# r3eflow-v1-outdated.net
KiCad netlist of a schematic drawn in EAGLE
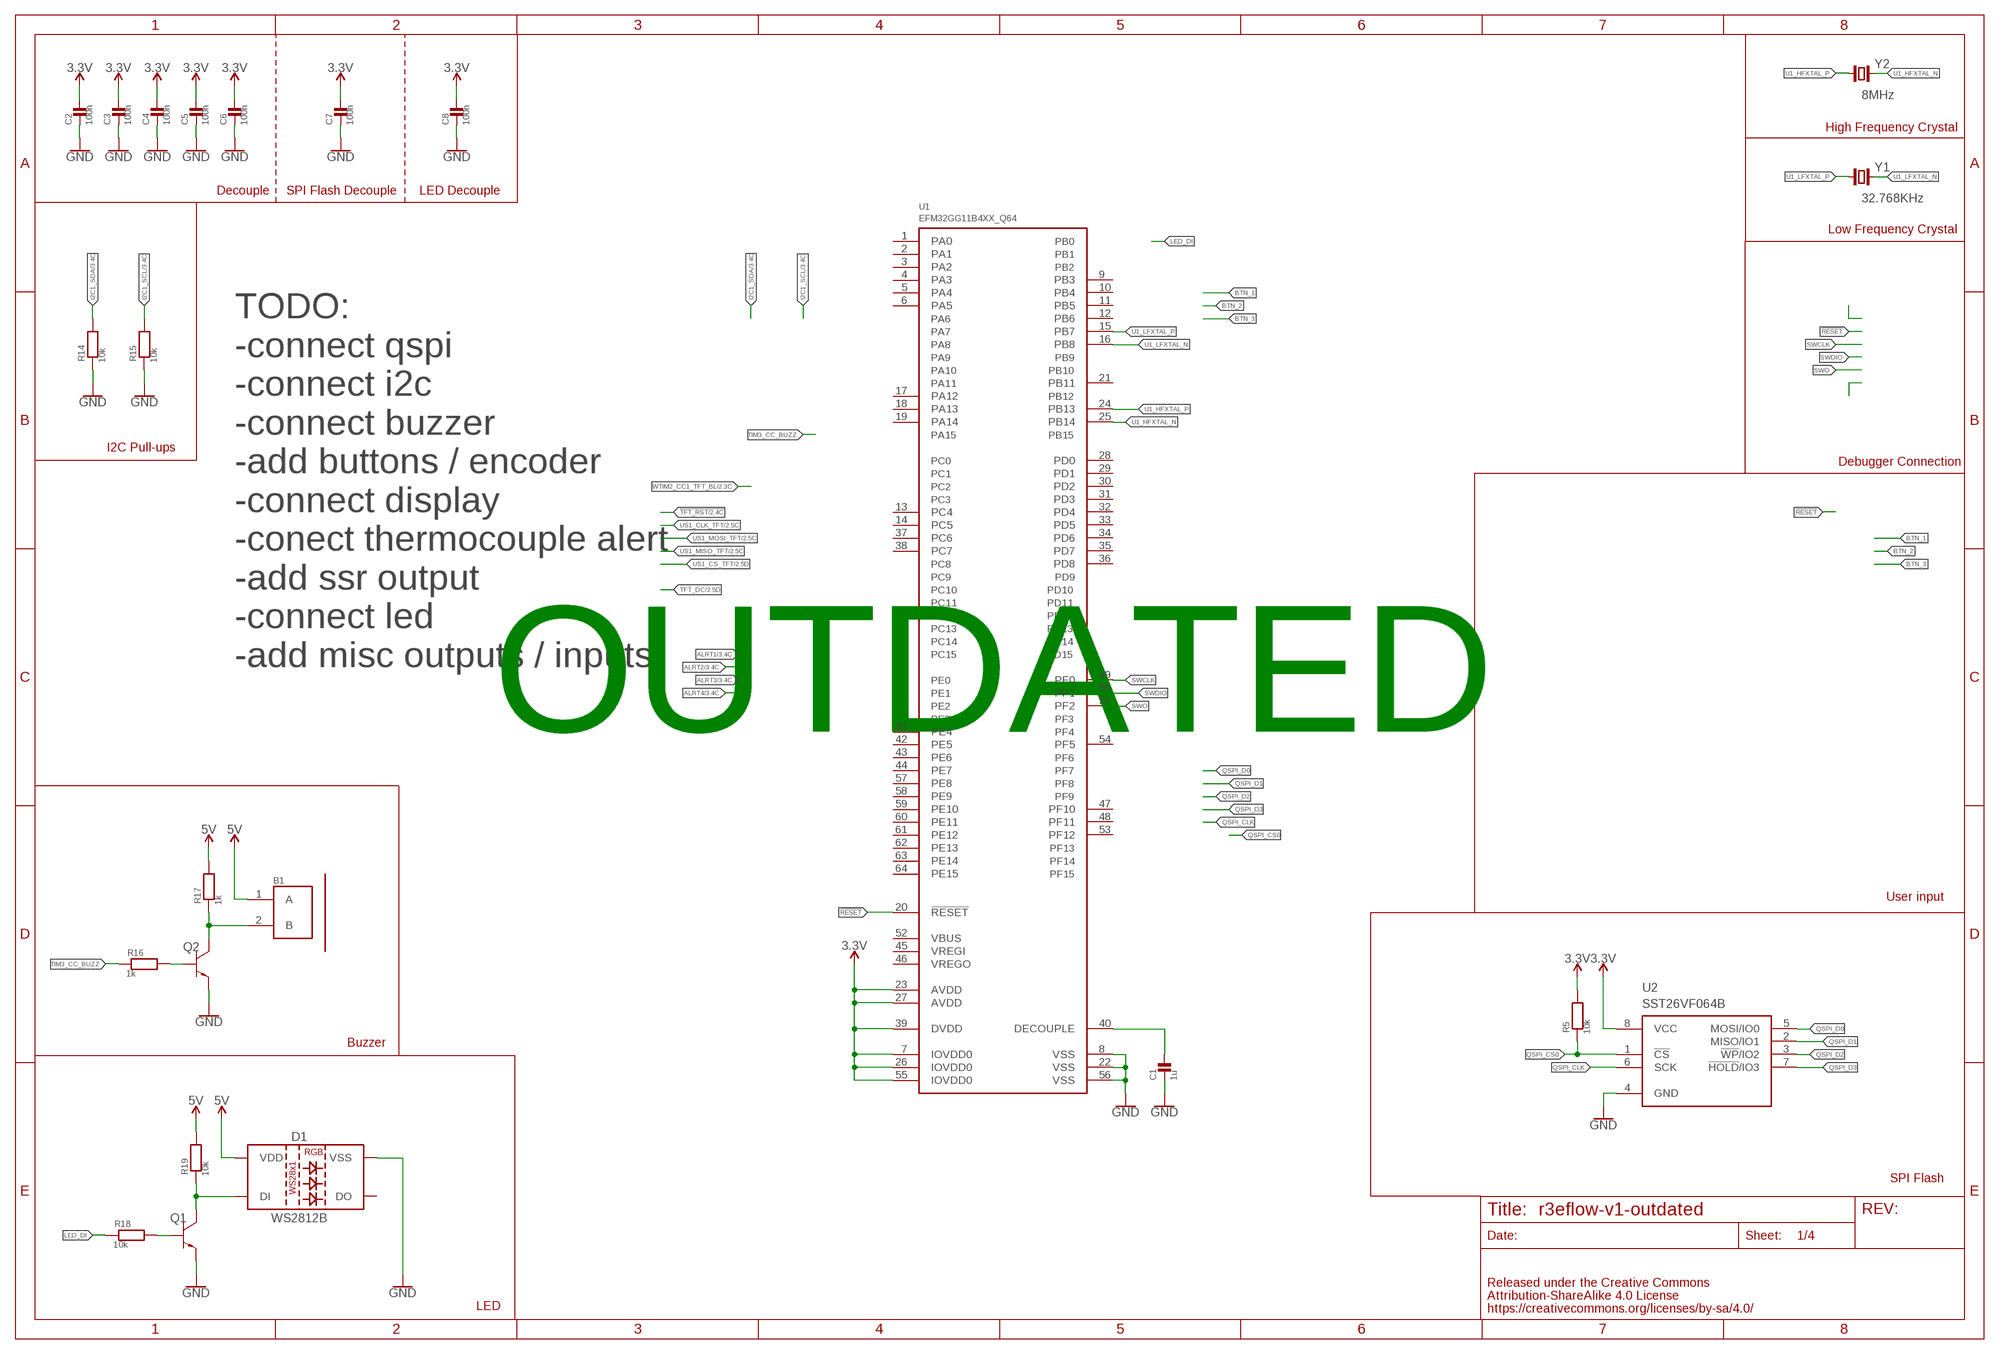
[diagram p0: schematic, sheet 1]
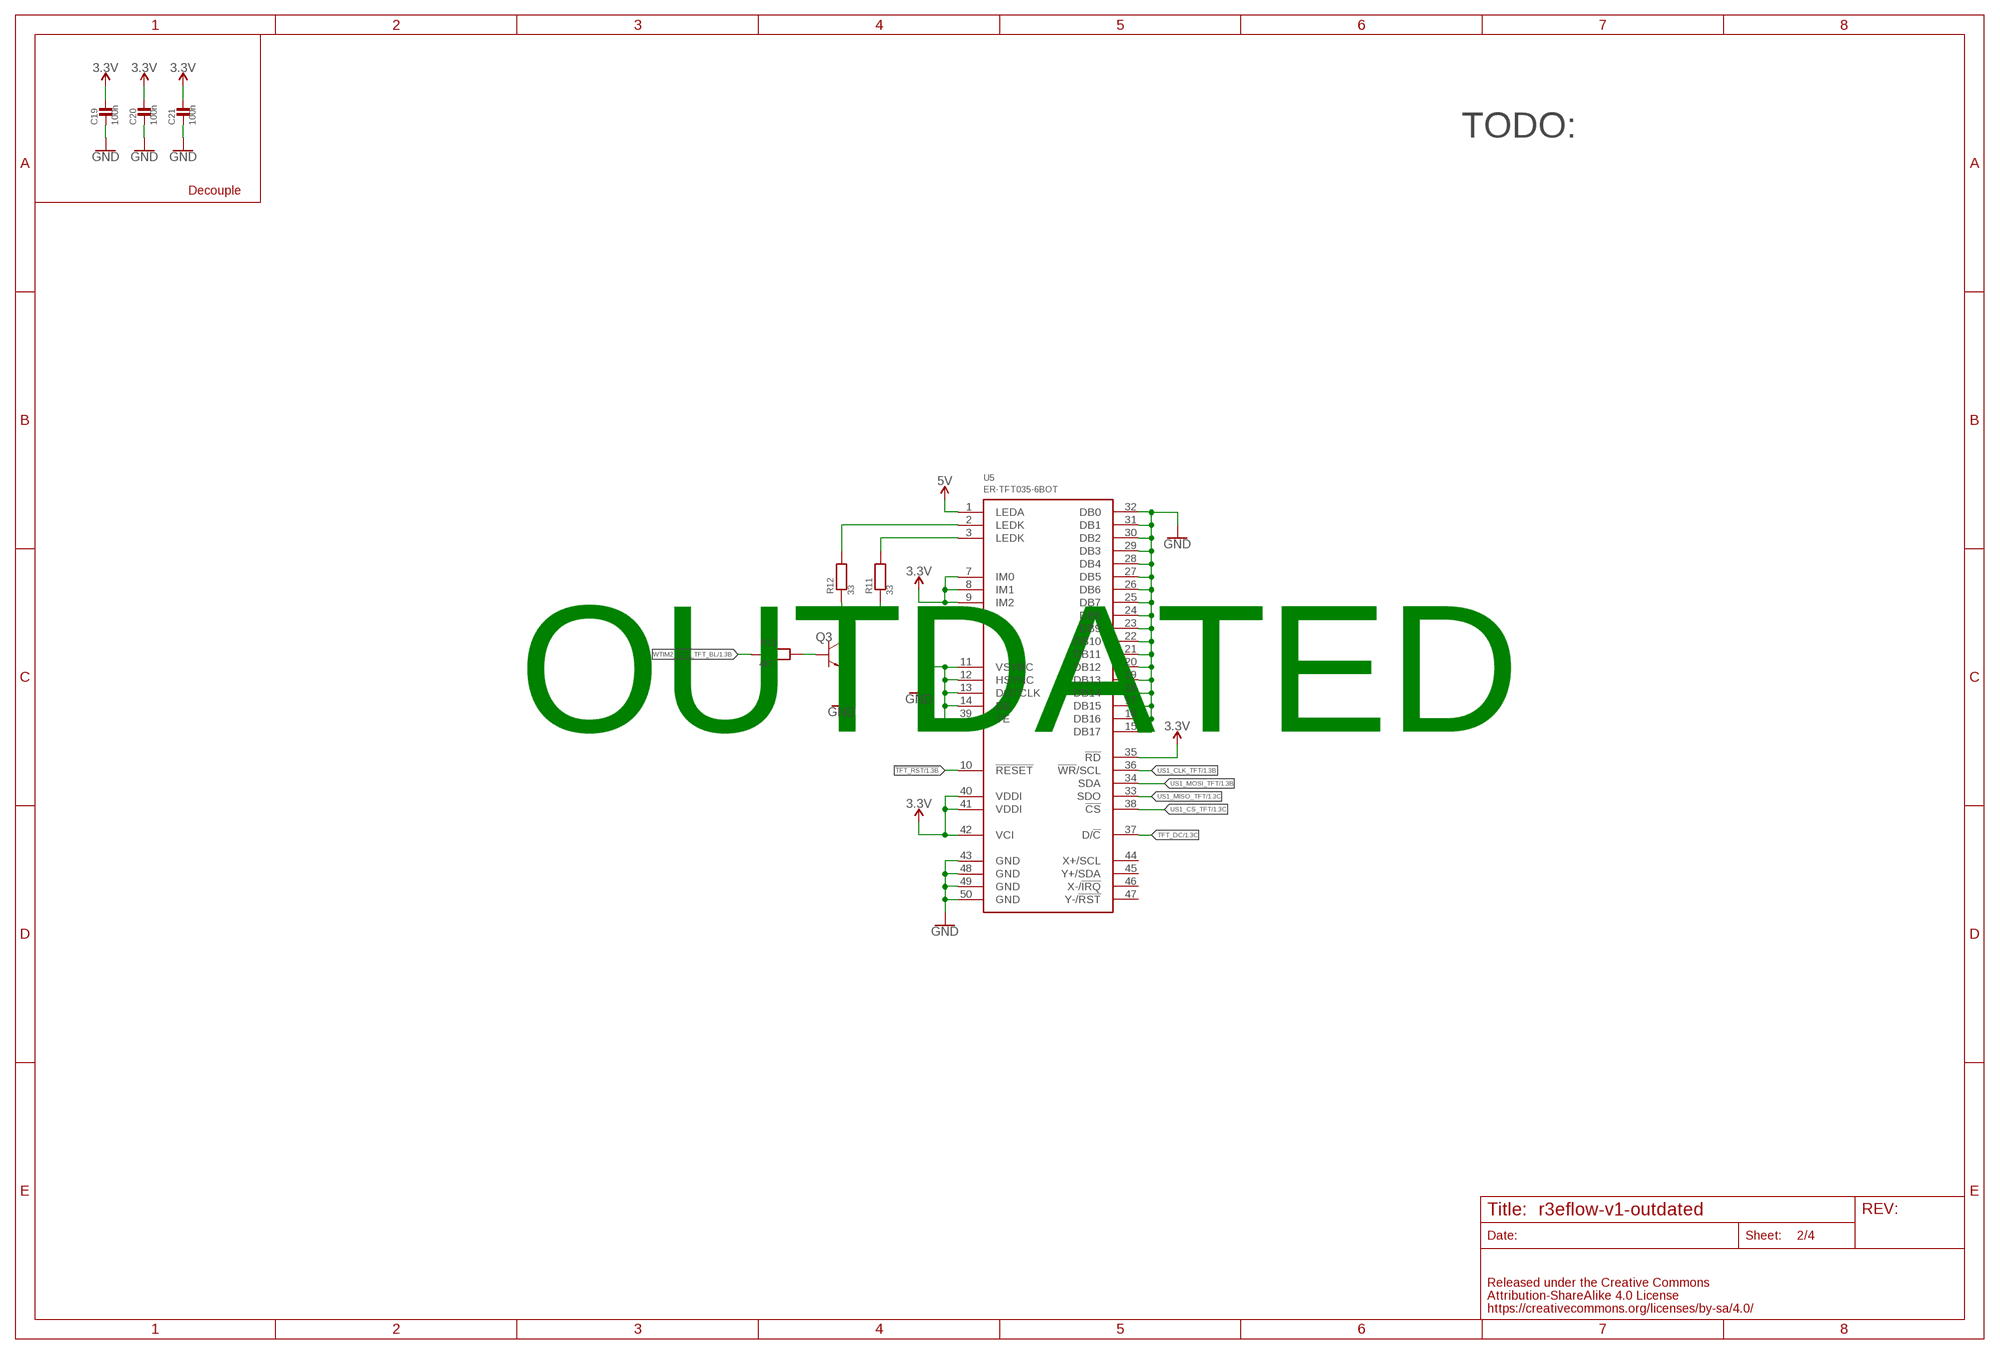
[diagram p1: schematic, sheet 2]
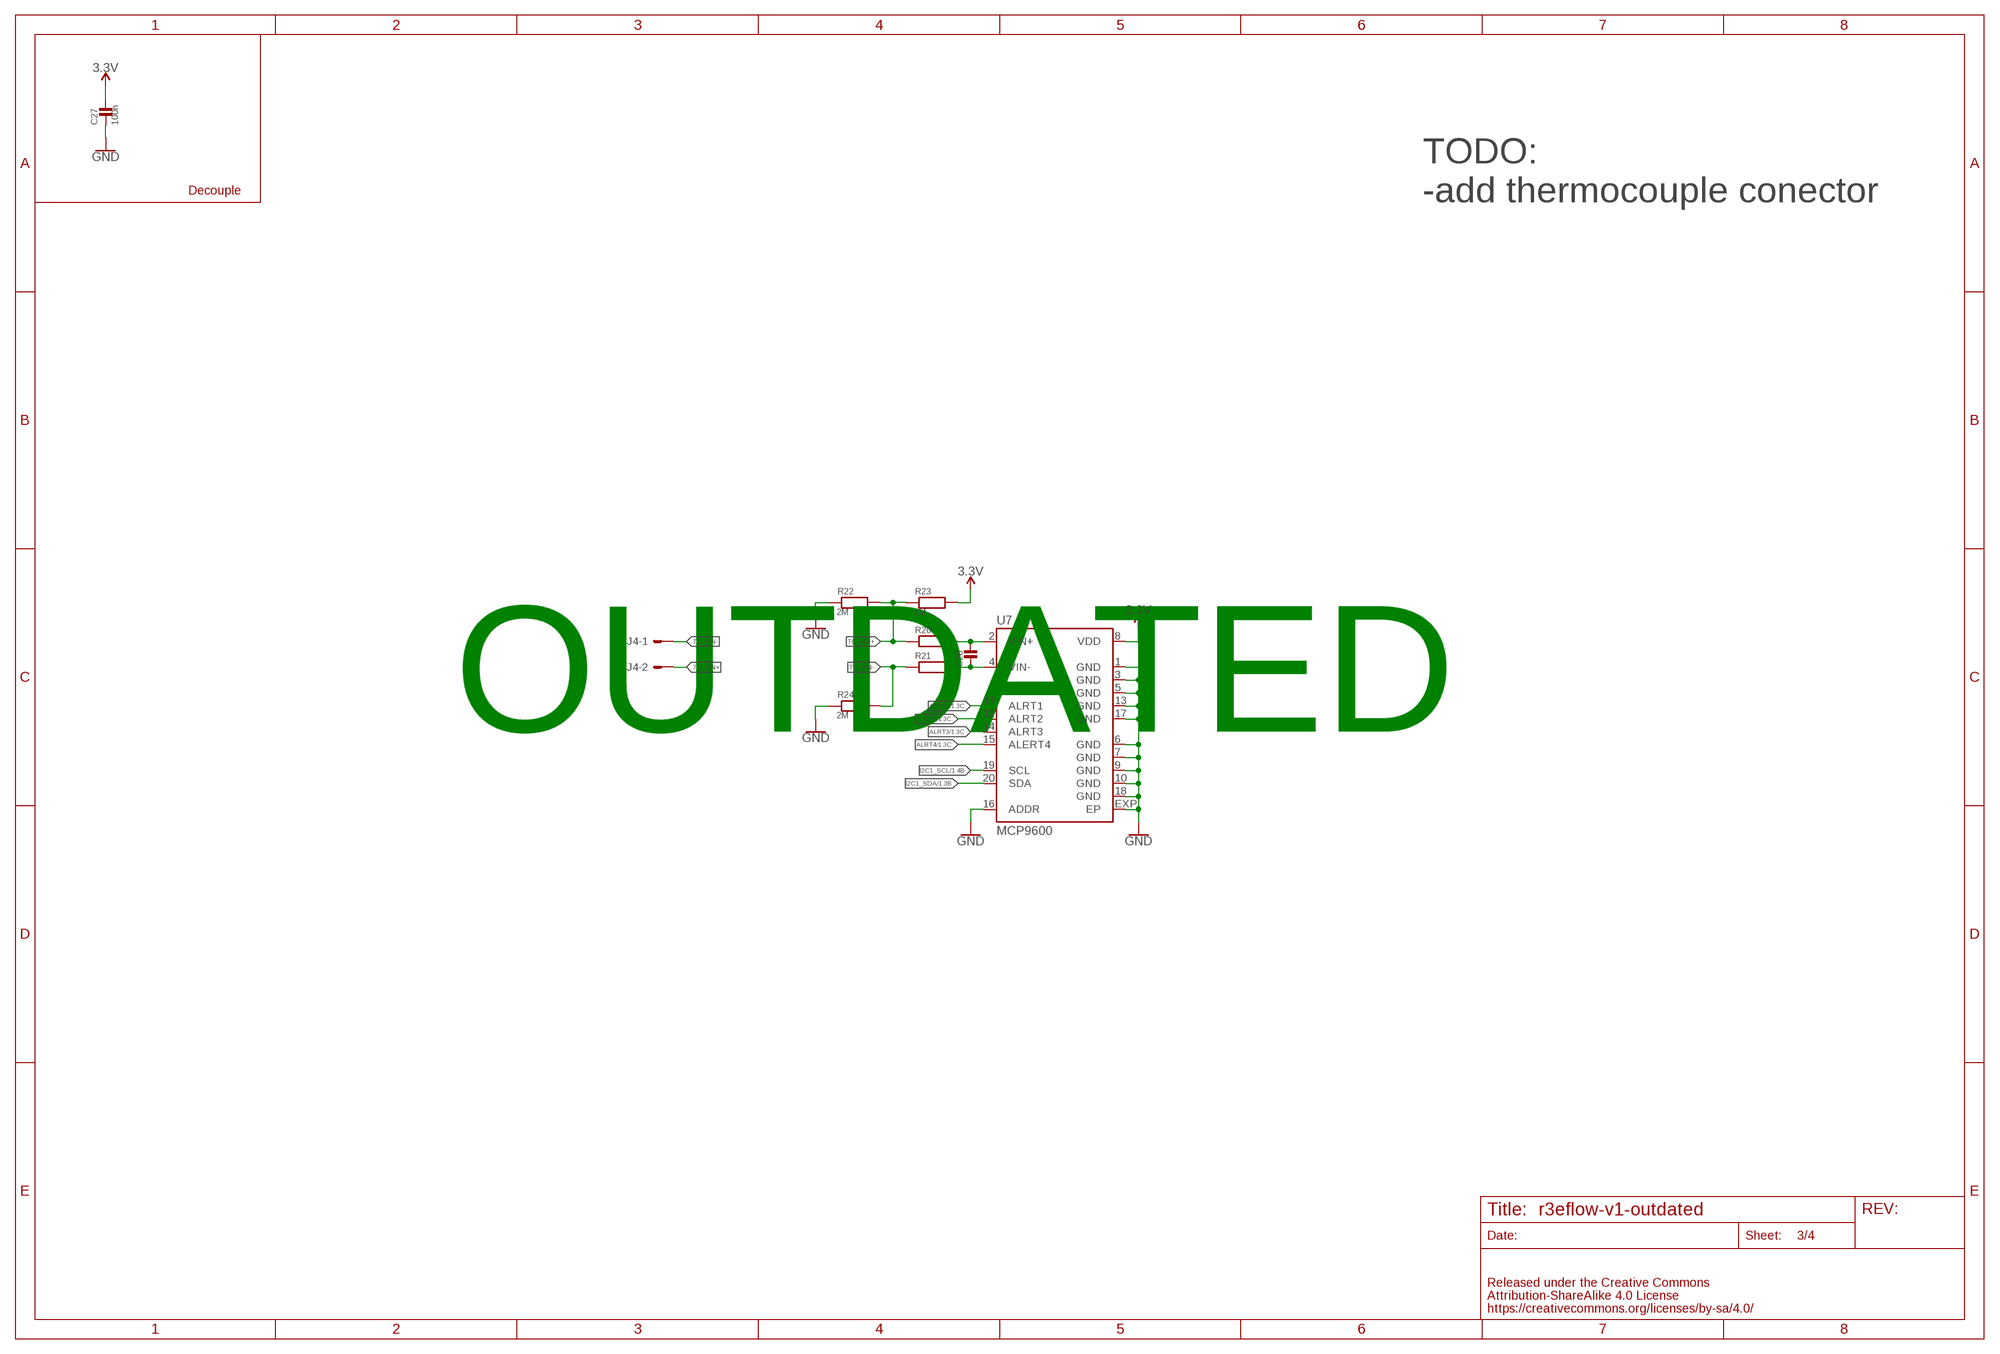
[diagram p2: schematic, sheet 3]
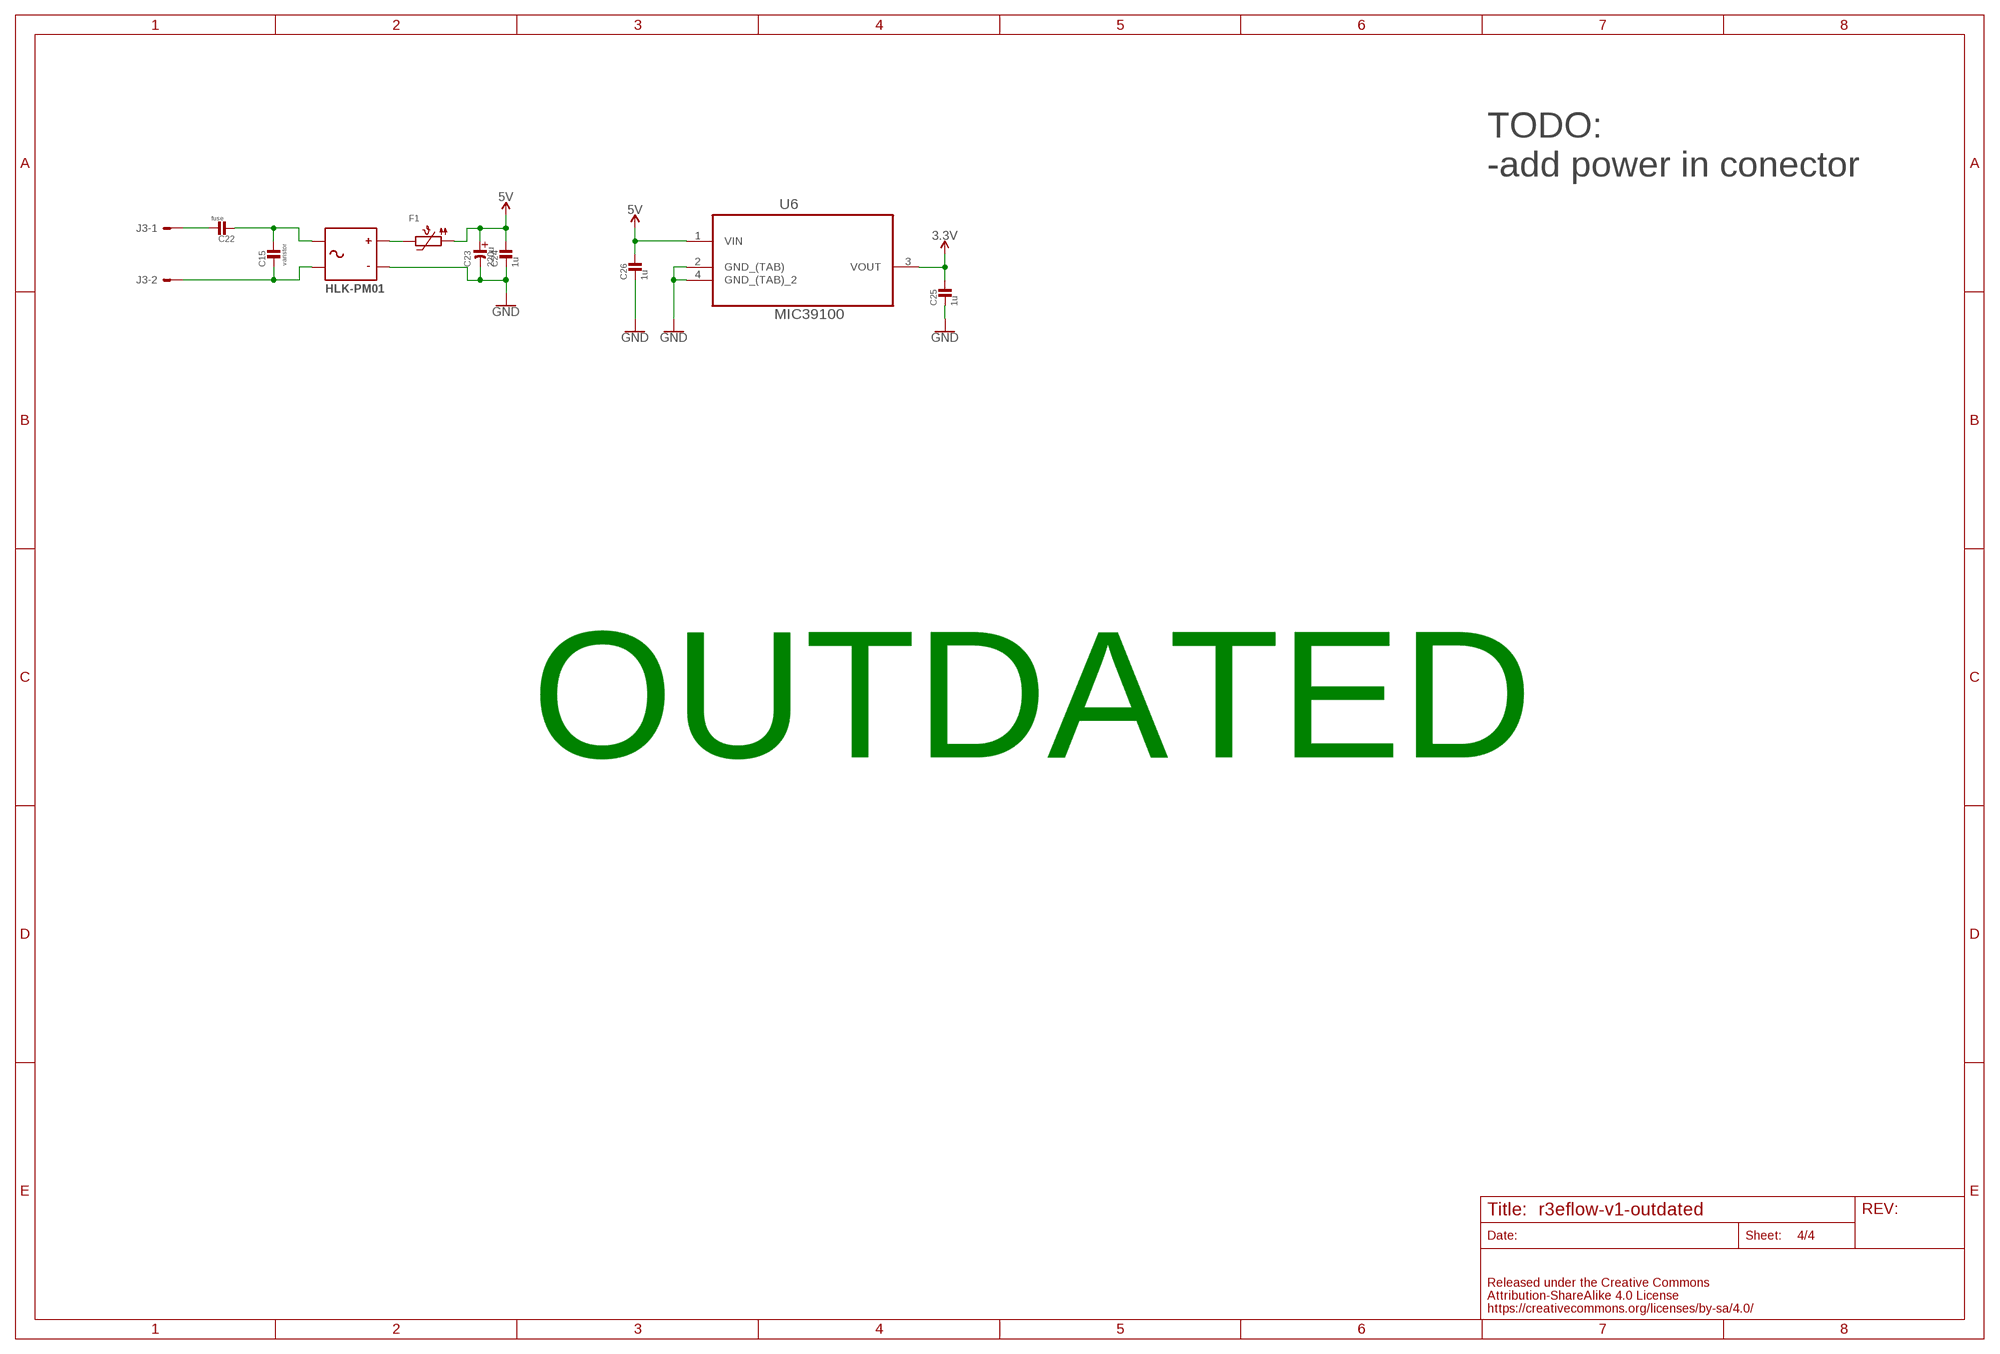
[diagram p3: schematic, sheet 4]

(export (version "E")
  (design (tool "Eeschema 10.0.6"))
  (components
    (comp (ref "C19")
      (value "100n")
      (footprint "eagle-import:0603_WAVE")
      (libsource (lib "eagle-import") (part "CAPACITOR_C0603"))
    )
    (comp (ref "C20")
      (value "100n")
      (footprint "eagle-import:0603_WAVE")
      (libsource (lib "eagle-import") (part "CAPACITOR_C0603"))
    )
    (comp (ref "C21")
      (value "100n")
      (footprint "eagle-import:0603_WAVE")
      (libsource (lib "eagle-import") (part "CAPACITOR_C0603"))
    )
    (comp (ref "Q3")
      (value "BC817-40")
      (footprint "eagle-import:SOT-23-3")
      (libsource (lib "eagle-import") (part "BC817-40"))
    )
    (comp (ref "R11")
      (value "33")
      (footprint "eagle-import:0603_WAVE")
      (libsource (lib "eagle-import") (part "RESISTOR0603"))
    )
    (comp (ref "R12")
      (value "33")
      (footprint "eagle-import:0603_WAVE")
      (libsource (lib "eagle-import") (part "RESISTOR0603"))
    )
    (comp (ref "R13")
      (value "4k7")
      (footprint "eagle-import:0603_WAVE")
      (libsource (lib "eagle-import") (part "RESISTOR0603"))
    )
    (comp (ref "U5")
      (value "ER-TFT035-6BOT")
      (footprint "eagle-import:ZIF50-TFT_BACK")
      (libsource (lib "eagle-import") (part "ER-TFT035-6BOT"))
    )
    (comp (ref "B1")
      (value "PKLCS1212E2400-R1")
      (footprint "eagle-import:BUZZ_PIEZO_SMD")
      (libsource (lib "eagle-import") (part "PKLCS1212E2400-R1"))
    )
    (comp (ref "C1")
      (value "1u")
      (footprint "eagle-import:0603_WAVE")
      (libsource (lib "eagle-import") (part "CAPACITOR_C0603"))
    )
    (comp (ref "C2")
      (value "100n")
      (footprint "eagle-import:0603_WAVE")
      (libsource (lib "eagle-import") (part "CAPACITOR_C0603"))
    )
    (comp (ref "C3")
      (value "100n")
      (footprint "eagle-import:0603_WAVE")
      (libsource (lib "eagle-import") (part "CAPACITOR_C0603"))
    )
    (comp (ref "C4")
      (value "100n")
      (footprint "eagle-import:0603_WAVE")
      (libsource (lib "eagle-import") (part "CAPACITOR_C0603"))
    )
    (comp (ref "C5")
      (value "100n")
      (footprint "eagle-import:0603_WAVE")
      (libsource (lib "eagle-import") (part "CAPACITOR_C0603"))
    )
    (comp (ref "C6")
      (value "100n")
      (footprint "eagle-import:0603_WAVE")
      (libsource (lib "eagle-import") (part "CAPACITOR_C0603"))
    )
    (comp (ref "C7")
      (value "100n")
      (footprint "eagle-import:0603_WAVE")
      (libsource (lib "eagle-import") (part "CAPACITOR_C0603"))
    )
    (comp (ref "C8")
      (value "100n")
      (footprint "eagle-import:0603_WAVE")
      (libsource (lib "eagle-import") (part "CAPACITOR_C0603"))
    )
    (comp (ref "D1")
      (value "WS2812B")
      (footprint "eagle-import:WS2812B")
      (libsource (lib "eagle-import") (part "WS2812B"))
    )
    (comp (ref "Q1")
      (value "BC817-40")
      (footprint "eagle-import:SOT-23-3")
      (libsource (lib "eagle-import") (part "BC817-40"))
    )
    (comp (ref "Q2")
      (value "BC817-40")
      (footprint "eagle-import:SOT-23-3")
      (libsource (lib "eagle-import") (part "BC817-40"))
    )
    (comp (ref "R5")
      (value "10k")
      (footprint "eagle-import:0603_WAVE")
      (libsource (lib "eagle-import") (part "RESISTOR0603"))
    )
    (comp (ref "R14")
      (value "10k")
      (footprint "eagle-import:0603_WAVE")
      (libsource (lib "eagle-import") (part "RESISTOR0603"))
    )
    (comp (ref "R15")
      (value "10k")
      (footprint "eagle-import:0603_WAVE")
      (libsource (lib "eagle-import") (part "RESISTOR0603"))
    )
    (comp (ref "R16")
      (value "1k")
      (footprint "eagle-import:0603_WAVE")
      (libsource (lib "eagle-import") (part "RESISTOR0603"))
    )
    (comp (ref "R17")
      (value "1k")
      (footprint "eagle-import:0603_WAVE")
      (libsource (lib "eagle-import") (part "RESISTOR0603"))
    )
    (comp (ref "R18")
      (value "10k")
      (footprint "eagle-import:0603_WAVE")
      (libsource (lib "eagle-import") (part "RESISTOR0603"))
    )
    (comp (ref "R19")
      (value "10k")
      (footprint "eagle-import:0603_WAVE")
      (libsource (lib "eagle-import") (part "RESISTOR0603"))
    )
    (comp (ref "U1")
      (value "EFM32GG11B4XX_Q64")
      (footprint "eagle-import:QFP64")
      (libsource (lib "eagle-import") (part "EFM32GG11B4XX_Q64"))
    )
    (comp (ref "U2")
      (value "SST26VF064B")
      (footprint "eagle-import:WSOIC8")
      (libsource (lib "eagle-import") (part "SST26VF064B"))
    )
    (comp (ref "Y1")
      (value "32.768KHz")
      (footprint "eagle-import:CM200S")
      (libsource (lib "eagle-import") (part "CRYSTALCM200S"))
    )
    (comp (ref "Y2")
      (value "8MHz")
      (footprint "eagle-import:2-SMD-5X3")
      (libsource (lib "eagle-import") (part "CRYSTALNX5032GA"))
    )
    (comp (ref "C27")
      (value "100n")
      (footprint "eagle-import:0603_WAVE")
      (libsource (lib "eagle-import") (part "CAPACITOR_C0603"))
    )
    (comp (ref "C28")
      (value "CAPACITOR_C0603")
      (footprint "eagle-import:0603_WAVE")
      (libsource (lib "eagle-import") (part "CAPACITOR_C0603"))
    )
    (comp (ref "J4")
      (value "1X2SPATF_1/2-3,5-IL")
      (footprint "eagle-import:SPTAF_1_2-3,5-IL")
      (libsource (lib "eagle-import") (part "1X2SPATF_1/2-3,5-IL"))
    )
    (comp (ref "R20")
      (value "RESISTOR0603")
      (footprint "eagle-import:0603_WAVE")
      (libsource (lib "eagle-import") (part "RESISTOR0603"))
    )
    (comp (ref "R21")
      (value "RESISTOR0603")
      (footprint "eagle-import:0603_WAVE")
      (libsource (lib "eagle-import") (part "RESISTOR0603"))
    )
    (comp (ref "R22")
      (value "2M")
      (footprint "eagle-import:0603_WAVE")
      (libsource (lib "eagle-import") (part "RESISTOR0603"))
    )
    (comp (ref "R23")
      (value "1M")
      (footprint "eagle-import:0603_WAVE")
      (libsource (lib "eagle-import") (part "RESISTOR0603"))
    )
    (comp (ref "R24")
      (value "2M")
      (footprint "eagle-import:0603_WAVE")
      (libsource (lib "eagle-import") (part "RESISTOR0603"))
    )
    (comp (ref "U7")
      (value "MCP9600")
      (footprint "eagle-import:TQFN20-5X5")
      (libsource (lib "eagle-import") (part "MCP9600"))
    )
    (comp (ref "C15")
      (value "CAPACITOR_CTH_15MM")
      (footprint "eagle-import:15MM")
      (libsource (lib "eagle-import") (part "CAPACITOR_CTH_15MM"))
    )
    (comp (ref "C22")
      (value "CAPACITOR_CTH_15MM")
      (footprint "eagle-import:15MM")
      (libsource (lib "eagle-import") (part "CAPACITOR_CTH_15MM"))
    )
    (comp (ref "C23")
      (value "220u")
      (footprint "eagle-import:G")
      (libsource (lib "eagle-import") (part "CAPACITOR_EL10X10"))
    )
    (comp (ref "C24")
      (value "1u")
      (footprint "eagle-import:0603_WAVE")
      (libsource (lib "eagle-import") (part "CAPACITOR_C0603"))
    )
    (comp (ref "C25")
      (value "1u")
      (footprint "eagle-import:0603_WAVE")
      (libsource (lib "eagle-import") (part "CAPACITOR_C0603"))
    )
    (comp (ref "C26")
      (value "1u")
      (footprint "eagle-import:0603_WAVE")
      (libsource (lib "eagle-import") (part "CAPACITOR_C0603"))
    )
    (comp (ref "F1")
      (value "PTC1812")
      (footprint "eagle-import:PTC1812")
      (libsource (lib "eagle-import") (part "PTC1812"))
    )
    (comp (ref "J3")
      (value "1X2SPATF_1/2-3,5-IL")
      (footprint "eagle-import:SPTAF_1_2-3,5-IL")
      (libsource (lib "eagle-import") (part "1X2SPATF_1/2-3,5-IL"))
    )
    (comp (ref "U$1")
      (value "HLK-PM01")
      (footprint "eagle-import:HLK-PM01")
      (libsource (lib "eagle-import") (part "HLK-PM01"))
    )
    (comp (ref "U6")
      (value "MIC39100")
      (footprint "eagle-import:SOT230P700X180-4N")
      (fields (field (name "MPN") "MCP1824ST-3302E/DB"))
      (libsource (lib "eagle-import") (part "MIC39100"))
    )
  )
  (nets
    (net (code "1") (name "3.3V") (class "Default")
      (node (ref "C19") (pin "P$1") (pinfunction "P$1_P$1") (pintype "bidirectional"))
      (node (ref "C2") (pin "P$1") (pinfunction "P$1_P$1") (pintype "bidirectional"))
      (node (ref "C20") (pin "P$1") (pinfunction "P$1_P$1") (pintype "bidirectional"))
      (node (ref "C21") (pin "P$1") (pinfunction "P$1_P$1") (pintype "bidirectional"))
      (node (ref "C25") (pin "P$1") (pinfunction "P$1_P$1") (pintype "bidirectional"))
      (node (ref "C27") (pin "P$1") (pinfunction "P$1_P$1") (pintype "bidirectional"))
      (node (ref "C3") (pin "P$1") (pinfunction "P$1_P$1") (pintype "bidirectional"))
      (node (ref "C4") (pin "P$1") (pinfunction "P$1_P$1") (pintype "bidirectional"))
      (node (ref "C5") (pin "P$1") (pinfunction "P$1_P$1") (pintype "bidirectional"))
      (node (ref "C6") (pin "P$1") (pinfunction "P$1_P$1") (pintype "bidirectional"))
      (node (ref "C7") (pin "P$1") (pinfunction "P$1_P$1") (pintype "bidirectional"))
      (node (ref "C8") (pin "P$1") (pinfunction "P$1_P$1") (pintype "bidirectional"))
      (node (ref "R23") (pin "P$2") (pinfunction "P$2_P$2") (pintype "bidirectional"))
      (node (ref "R5") (pin "P$2") (pinfunction "P$2_P$2") (pintype "bidirectional"))
      (node (ref "U1") (pin "23") (pinfunction "AVDD_23") (pintype "bidirectional"))
      (node (ref "U1") (pin "26") (pinfunction "IOVDD0_26") (pintype "bidirectional"))
      (node (ref "U1") (pin "27") (pinfunction "AVDD_27") (pintype "bidirectional"))
      (node (ref "U1") (pin "39") (pinfunction "DVDD_39") (pintype "bidirectional"))
      (node (ref "U1") (pin "55") (pinfunction "IOVDD0_55") (pintype "bidirectional"))
      (node (ref "U1") (pin "7") (pinfunction "IOVDD0_7") (pintype "bidirectional"))
      (node (ref "U2") (pin "8") (pinfunction "VCC_8") (pintype "power_in"))
      (node (ref "U5") (pin "35") (pinfunction "~{RD}_35") (pintype "bidirectional"))
      (node (ref "U5") (pin "40") (pinfunction "VDDI_40") (pintype "bidirectional"))
      (node (ref "U5") (pin "41") (pinfunction "VDDI_41") (pintype "bidirectional"))
      (node (ref "U5") (pin "42") (pinfunction "VCI_42") (pintype "bidirectional"))
      (node (ref "U5") (pin "7") (pinfunction "IM0_7") (pintype "bidirectional"))
      (node (ref "U5") (pin "8") (pinfunction "IM1_8") (pintype "bidirectional"))
      (node (ref "U5") (pin "9") (pinfunction "IM2_9") (pintype "bidirectional"))
      (node (ref "U6") (pin "3") (pinfunction "VOUT_3") (pintype "bidirectional"))
      (node (ref "U7") (pin "8") (pinfunction "VDD_8") (pintype "bidirectional"))
    )
    (net (code "2") (name "5V") (class "Default")
      (node (ref "B1") (pin "1") (pinfunction "A_1") (pintype "bidirectional"))
      (node (ref "C23") (pin "AN") (pinfunction "AN_AN") (pintype "bidirectional"))
      (node (ref "C24") (pin "P$1") (pinfunction "P$1_P$1") (pintype "bidirectional"))
      (node (ref "C26") (pin "P$1") (pinfunction "P$1_P$1") (pintype "bidirectional"))
      (node (ref "D1") (pin "1") (pinfunction "VDD_1") (pintype "bidirectional"))
      (node (ref "F1") (pin "P$1") (pinfunction "1_P$1") (pintype "passive"))
      (node (ref "R17") (pin "P$2") (pinfunction "P$2_P$2") (pintype "bidirectional"))
      (node (ref "R19") (pin "P$2") (pinfunction "P$2_P$2") (pintype "bidirectional"))
      (node (ref "U5") (pin "1") (pinfunction "LEDA_1") (pintype "bidirectional"))
      (node (ref "U6") (pin "1") (pinfunction "VIN_1") (pintype "input"))
    )
    (net (code "3") (name "ALRT1") (class "Default")
      (node (ref "U7") (pin "11") (pinfunction "ALRT1_11") (pintype "bidirectional"))
    )
    (net (code "4") (name "ALRT2") (class "Default")
      (node (ref "U7") (pin "12") (pinfunction "ALRT2_12") (pintype "bidirectional"))
    )
    (net (code "5") (name "ALRT3") (class "Default")
      (node (ref "U7") (pin "14") (pinfunction "ALRT3_14") (pintype "bidirectional"))
    )
    (net (code "6") (name "ALRT4") (class "Default")
      (node (ref "U7") (pin "15") (pinfunction "ALERT4_15") (pintype "bidirectional"))
    )
    (net (code "10") (name "GND") (class "Default")
      (node (ref "C1") (pin "P$2") (pinfunction "P$2_P$2") (pintype "bidirectional"))
      (node (ref "C19") (pin "P$2") (pinfunction "P$2_P$2") (pintype "bidirectional"))
      (node (ref "C2") (pin "P$2") (pinfunction "P$2_P$2") (pintype "bidirectional"))
      (node (ref "C20") (pin "P$2") (pinfunction "P$2_P$2") (pintype "bidirectional"))
      (node (ref "C21") (pin "P$2") (pinfunction "P$2_P$2") (pintype "bidirectional"))
      (node (ref "C23") (pin "CAT") (pinfunction "CA_CAT") (pintype "bidirectional"))
      (node (ref "C24") (pin "P$2") (pinfunction "P$2_P$2") (pintype "bidirectional"))
      (node (ref "C25") (pin "P$2") (pinfunction "P$2_P$2") (pintype "bidirectional"))
      (node (ref "C26") (pin "P$2") (pinfunction "P$2_P$2") (pintype "bidirectional"))
      (node (ref "C27") (pin "P$2") (pinfunction "P$2_P$2") (pintype "bidirectional"))
      (node (ref "C3") (pin "P$2") (pinfunction "P$2_P$2") (pintype "bidirectional"))
      (node (ref "C4") (pin "P$2") (pinfunction "P$2_P$2") (pintype "bidirectional"))
      (node (ref "C5") (pin "P$2") (pinfunction "P$2_P$2") (pintype "bidirectional"))
      (node (ref "C6") (pin "P$2") (pinfunction "P$2_P$2") (pintype "bidirectional"))
      (node (ref "C7") (pin "P$2") (pinfunction "P$2_P$2") (pintype "bidirectional"))
      (node (ref "C8") (pin "P$2") (pinfunction "P$2_P$2") (pintype "bidirectional"))
      (node (ref "D1") (pin "3") (pinfunction "VSS_3") (pintype "bidirectional"))
      (node (ref "Q1") (pin "P$2") (pinfunction "EM2_P$2") (pintype "bidirectional"))
      (node (ref "Q2") (pin "P$2") (pinfunction "EM2_P$2") (pintype "bidirectional"))
      (node (ref "Q3") (pin "P$2") (pinfunction "EM2_P$2") (pintype "bidirectional"))
      (node (ref "R14") (pin "P$1") (pinfunction "P$1_P$1") (pintype "bidirectional"))
      (node (ref "R15") (pin "P$1") (pinfunction "P$1_P$1") (pintype "bidirectional"))
      (node (ref "R22") (pin "P$1") (pinfunction "P$1_P$1") (pintype "bidirectional"))
      (node (ref "R24") (pin "P$1") (pinfunction "P$1_P$1") (pintype "bidirectional"))
      (node (ref "U$1") (pin "-VO") (pinfunction "-VO_-VO") (pintype "bidirectional"))
      (node (ref "U1") (pin "22") (pinfunction "VSS_22") (pintype "bidirectional"))
      (node (ref "U1") (pin "56") (pinfunction "VSS_56") (pintype "bidirectional"))
      (node (ref "U1") (pin "8") (pinfunction "VSS_8") (pintype "bidirectional"))
      (node (ref "U2") (pin "4") (pinfunction "GND_4") (pintype "power_in"))
      (node (ref "U5") (pin "11") (pinfunction "VSYNC_11") (pintype "bidirectional"))
      (node (ref "U5") (pin "12") (pinfunction "HSYNC_12") (pintype "bidirectional"))
      (node (ref "U5") (pin "13") (pinfunction "DOTCLK_13") (pintype "bidirectional"))
      (node (ref "U5") (pin "14") (pinfunction "DE_14") (pintype "bidirectional"))
      (node (ref "U5") (pin "15") (pinfunction "DB17_15") (pintype "bidirectional"))
      (node (ref "U5") (pin "16") (pinfunction "DB16_16") (pintype "bidirectional"))
      (node (ref "U5") (pin "17") (pinfunction "DB15_17") (pintype "bidirectional"))
      (node (ref "U5") (pin "18") (pinfunction "DB14_18") (pintype "bidirectional"))
      (node (ref "U5") (pin "19") (pinfunction "DB13_19") (pintype "bidirectional"))
      (node (ref "U5") (pin "20") (pinfunction "DB12_20") (pintype "bidirectional"))
      (node (ref "U5") (pin "21") (pinfunction "DB11_21") (pintype "bidirectional"))
      (node (ref "U5") (pin "22") (pinfunction "DB10_22") (pintype "bidirectional"))
      (node (ref "U5") (pin "23") (pinfunction "DB9_23") (pintype "bidirectional"))
      (node (ref "U5") (pin "24") (pinfunction "DB8_24") (pintype "bidirectional"))
      (node (ref "U5") (pin "25") (pinfunction "DB7_25") (pintype "bidirectional"))
      (node (ref "U5") (pin "26") (pinfunction "DB6_26") (pintype "bidirectional"))
      (node (ref "U5") (pin "27") (pinfunction "DB5_27") (pintype "bidirectional"))
      (node (ref "U5") (pin "28") (pinfunction "DB4_28") (pintype "bidirectional"))
      (node (ref "U5") (pin "29") (pinfunction "DB3_29") (pintype "bidirectional"))
      (node (ref "U5") (pin "30") (pinfunction "DB2_30") (pintype "bidirectional"))
      (node (ref "U5") (pin "31") (pinfunction "DB1_31") (pintype "bidirectional"))
      (node (ref "U5") (pin "32") (pinfunction "DB0_32") (pintype "bidirectional"))
      (node (ref "U5") (pin "39") (pinfunction "TE_39") (pintype "bidirectional"))
      (node (ref "U5") (pin "43") (pinfunction "GND_43") (pintype "bidirectional"))
      (node (ref "U5") (pin "48") (pinfunction "GND_48") (pintype "bidirectional"))
      (node (ref "U5") (pin "49") (pinfunction "GND_49") (pintype "bidirectional"))
      (node (ref "U5") (pin "50") (pinfunction "GND_50") (pintype "bidirectional"))
      (node (ref "U6") (pin "2") (pinfunction "GND_(TAB)_2") (pintype "bidirectional"))
      (node (ref "U6") (pin "4") (pinfunction "GND_(TAB)_2_4") (pintype "bidirectional"))
      (node (ref "U7") (pin "1") (pinfunction "GND_1") (pintype "bidirectional"))
      (node (ref "U7") (pin "10") (pinfunction "GND_10") (pintype "bidirectional"))
      (node (ref "U7") (pin "13") (pinfunction "GND_13") (pintype "bidirectional"))
      (node (ref "U7") (pin "16") (pinfunction "ADDR_16") (pintype "bidirectional"))
      (node (ref "U7") (pin "17") (pinfunction "GND_17") (pintype "bidirectional"))
      (node (ref "U7") (pin "18") (pinfunction "GND_18") (pintype "bidirectional"))
      (node (ref "U7") (pin "3") (pinfunction "GND_3") (pintype "bidirectional"))
      (node (ref "U7") (pin "5") (pinfunction "GND_5") (pintype "bidirectional"))
      (node (ref "U7") (pin "6") (pinfunction "GND_6") (pintype "bidirectional"))
      (node (ref "U7") (pin "7") (pinfunction "GND_7") (pintype "bidirectional"))
      (node (ref "U7") (pin "9") (pinfunction "GND_9") (pintype "bidirectional"))
      (node (ref "U7") (pin "EXP") (pinfunction "EP_EXP") (pintype "bidirectional"))
    )
    (net (code "11") (name "I2C1_SCL") (class "Default")
      (node (ref "R15") (pin "P$2") (pinfunction "P$2_P$2") (pintype "bidirectional"))
      (node (ref "U7") (pin "19") (pinfunction "SCL_19") (pintype "bidirectional"))
    )
    (net (code "12") (name "I2C1_SDA") (class "Default")
      (node (ref "R14") (pin "P$2") (pinfunction "P$2_P$2") (pintype "bidirectional"))
      (node (ref "U7") (pin "20") (pinfunction "SDA_20") (pintype "bidirectional"))
    )
    (net (code "13") (name "LED_DI") (class "Default")
      (node (ref "R18") (pin "P$1") (pinfunction "P$1_P$1") (pintype "bidirectional"))
    )
    (net (code "14") (name "Net-(B1-B)") (class "Default")
      (node (ref "B1") (pin "2") (pinfunction "B_2") (pintype "bidirectional"))
      (node (ref "Q2") (pin "P$3") (pinfunction "C03_P$3") (pintype "bidirectional"))
      (node (ref "R17") (pin "P$1") (pinfunction "P$1_P$1") (pintype "bidirectional"))
    )
    (net (code "15") (name "Net-(C15-PadP$1)") (class "Default")
      (node (ref "C15") (pin "P$1") (pinfunction "P$1_P$1") (pintype "bidirectional"))
      (node (ref "C22") (pin "P$2") (pinfunction "P$2_P$2") (pintype "bidirectional"))
      (node (ref "U$1") (pin "AC1") (pinfunction "AC1_AC1") (pintype "bidirectional"))
    )
    (net (code "16") (name "Net-(C15-PadP$2)") (class "Default")
      (node (ref "C15") (pin "P$2") (pinfunction "P$2_P$2") (pintype "bidirectional"))
      (node (ref "J3") (pin "P$2") (pinfunction "S_P$2") (pintype "passive"))
      (node (ref "J3") (pin "P$2'") (pinfunction "S_P$2'") (pintype "passive"))
      (node (ref "U$1") (pin "AC2") (pinfunction "AC2_AC2") (pintype "bidirectional"))
    )
    (net (code "17") (name "Net-(C22-PadP$1)") (class "Default")
      (node (ref "C22") (pin "P$1") (pinfunction "P$1_P$1") (pintype "bidirectional"))
      (node (ref "J3") (pin "P$1") (pinfunction "S_P$1") (pintype "passive"))
      (node (ref "J3") (pin "P$1'") (pinfunction "S_P$1'") (pintype "passive"))
    )
    (net (code "18") (name "Net-(D1-DI)") (class "Default")
      (node (ref "D1") (pin "4") (pinfunction "DI_4") (pintype "bidirectional"))
      (node (ref "Q1") (pin "P$3") (pinfunction "C03_P$3") (pintype "bidirectional"))
      (node (ref "R19") (pin "P$1") (pinfunction "P$1_P$1") (pintype "bidirectional"))
    )
    (net (code "19") (name "Net-(F1-2)") (class "Default")
      (node (ref "F1") (pin "P$2") (pinfunction "2_P$2") (pintype "passive"))
      (node (ref "U$1") (pin "+VO") (pinfunction "+VO_+VO") (pintype "bidirectional"))
    )
    (net (code "20") (name "Net-(Q1-BA1)") (class "Default")
      (node (ref "Q1") (pin "P$1") (pinfunction "BA1_P$1") (pintype "bidirectional"))
      (node (ref "R18") (pin "P$2") (pinfunction "P$2_P$2") (pintype "bidirectional"))
    )
    (net (code "21") (name "Net-(Q2-BA1)") (class "Default")
      (node (ref "Q2") (pin "P$1") (pinfunction "BA1_P$1") (pintype "bidirectional"))
      (node (ref "R16") (pin "P$2") (pinfunction "P$2_P$2") (pintype "bidirectional"))
    )
    (net (code "22") (name "Net-(Q3-BA1)") (class "Default")
      (node (ref "Q3") (pin "P$1") (pinfunction "BA1_P$1") (pintype "bidirectional"))
      (node (ref "R13") (pin "P$2") (pinfunction "P$2_P$2") (pintype "bidirectional"))
    )
    (net (code "23") (name "Net-(Q3-C03)") (class "Default")
      (node (ref "Q3") (pin "P$3") (pinfunction "C03_P$3") (pintype "bidirectional"))
      (node (ref "R11") (pin "P$1") (pinfunction "P$1_P$1") (pintype "bidirectional"))
      (node (ref "R12") (pin "P$1") (pinfunction "P$1_P$1") (pintype "bidirectional"))
    )
    (net (code "24") (name "Net-(R11-PadP$2)") (class "Default")
      (node (ref "R11") (pin "P$2") (pinfunction "P$2_P$2") (pintype "bidirectional"))
      (node (ref "U5") (pin "3") (pinfunction "LEDK_3") (pintype "bidirectional"))
    )
    (net (code "25") (name "Net-(R12-PadP$2)") (class "Default")
      (node (ref "R12") (pin "P$2") (pinfunction "P$2_P$2") (pintype "bidirectional"))
      (node (ref "U5") (pin "2") (pinfunction "LEDK_2") (pintype "bidirectional"))
    )
    (net (code "26") (name "Net-(U1-DECOUPLE)") (class "Default")
      (node (ref "C1") (pin "P$1") (pinfunction "P$1_P$1") (pintype "bidirectional"))
      (node (ref "U1") (pin "40") (pinfunction "DECOUPLE_40") (pintype "bidirectional"))
    )
    (net (code "27") (name "Net-(U7-VIN+)") (class "Default")
      (node (ref "C28") (pin "P$1") (pinfunction "P$1_P$1") (pintype "bidirectional"))
      (node (ref "R20") (pin "P$2") (pinfunction "P$2_P$2") (pintype "bidirectional"))
      (node (ref "U7") (pin "2") (pinfunction "VIN+_2") (pintype "bidirectional"))
    )
    (net (code "28") (name "Net-(U7-VIN-)") (class "Default")
      (node (ref "C28") (pin "P$2") (pinfunction "P$2_P$2") (pintype "bidirectional"))
      (node (ref "R21") (pin "P$2") (pinfunction "P$2_P$2") (pintype "bidirectional"))
      (node (ref "U7") (pin "4") (pinfunction "VIN-_4") (pintype "bidirectional"))
    )
    (net (code "29") (name "QSPI_CLK") (class "Default")
      (node (ref "U2") (pin "6") (pinfunction "SCK_6") (pintype "input"))
    )
    (net (code "30") (name "QSPI_CS0") (class "Default")
      (node (ref "R5") (pin "P$1") (pinfunction "P$1_P$1") (pintype "bidirectional"))
      (node (ref "U2") (pin "1") (pinfunction "~{CS}_1") (pintype "input"))
    )
    (net (code "31") (name "QSPI_D0") (class "Default")
      (node (ref "U2") (pin "5") (pinfunction "MOSI/IO0_5") (pintype "input"))
    )
    (net (code "32") (name "QSPI_D1") (class "Default")
      (node (ref "U2") (pin "2") (pinfunction "MISO/IO1_2") (pintype "output"))
    )
    (net (code "33") (name "QSPI_D2") (class "Default")
      (node (ref "U2") (pin "3") (pinfunction "~{WP}/IO2_3") (pintype "input"))
    )
    (net (code "34") (name "QSPI_D3") (class "Default")
      (node (ref "U2") (pin "7") (pinfunction "~{HOLD}/IO3_7") (pintype "input"))
    )
    (net (code "35") (name "SWCLK") (class "Default")
      (node (ref "U1") (pin "49") (pinfunction "PF0_49") (pintype "bidirectional"))
    )
    (net (code "36") (name "SWDIO") (class "Default")
      (node (ref "U1") (pin "50") (pinfunction "PF1_50") (pintype "bidirectional"))
    )
    (net (code "37") (name "SWO") (class "Default")
      (node (ref "U1") (pin "51") (pinfunction "PF2_51") (pintype "bidirectional"))
    )
    (net (code "38") (name "TC_VIN+") (class "Default")
      (node (ref "J4") (pin "P$2") (pinfunction "S_P$2") (pintype "passive"))
      (node (ref "J4") (pin "P$2'") (pinfunction "S_P$2'") (pintype "passive"))
      (node (ref "R20") (pin "P$1") (pinfunction "P$1_P$1") (pintype "bidirectional"))
      (node (ref "R22") (pin "P$2") (pinfunction "P$2_P$2") (pintype "bidirectional"))
      (node (ref "R23") (pin "P$1") (pinfunction "P$1_P$1") (pintype "bidirectional"))
    )
    (net (code "39") (name "TC_VIN-") (class "Default")
      (node (ref "J4") (pin "P$1") (pinfunction "S_P$1") (pintype "passive"))
      (node (ref "J4") (pin "P$1'") (pinfunction "S_P$1'") (pintype "passive"))
      (node (ref "R21") (pin "P$1") (pinfunction "P$1_P$1") (pintype "bidirectional"))
      (node (ref "R24") (pin "P$2") (pinfunction "P$2_P$2") (pintype "bidirectional"))
    )
    (net (code "40") (name "TFT_DC") (class "Default")
      (node (ref "U5") (pin "37") (pinfunction "D/~{C}_37") (pintype "bidirectional"))
    )
    (net (code "41") (name "TIM3_CC_BUZZ") (class "Default")
      (node (ref "R16") (pin "P$1") (pinfunction "P$1_P$1") (pintype "bidirectional"))
    )
    (net (code "42") (name "U1_HFXTAL_N") (class "Default")
      (node (ref "U1") (pin "25") (pinfunction "PB14_25") (pintype "bidirectional"))
      (node (ref "Y2") (pin "2") (pinfunction "2_2") (pintype "passive"))
    )
    (net (code "43") (name "U1_HFXTAL_P") (class "Default")
      (node (ref "U1") (pin "24") (pinfunction "PB13_24") (pintype "bidirectional"))
      (node (ref "Y2") (pin "1") (pinfunction "1_1") (pintype "passive"))
    )
    (net (code "44") (name "U1_LFXTAL_N") (class "Default")
      (node (ref "U1") (pin "16") (pinfunction "PB8_16") (pintype "bidirectional"))
      (node (ref "Y1") (pin "4") (pinfunction "2_4") (pintype "passive"))
    )
    (net (code "45") (name "U1_LFXTAL_P") (class "Default")
      (node (ref "U1") (pin "15") (pinfunction "PB7_15") (pintype "bidirectional"))
      (node (ref "Y1") (pin "1") (pinfunction "1_1") (pintype "passive"))
    )
    (net (code "46") (name "US1_CLK_TFT") (class "Default")
      (node (ref "U5") (pin "36") (pinfunction "~{WR}/SCL_36") (pintype "bidirectional"))
    )
    (net (code "47") (name "US1_CS_TFT") (class "Default")
      (node (ref "U5") (pin "38") (pinfunction "~{CS}_38") (pintype "bidirectional"))
    )
    (net (code "48") (name "US1_MISO_TFT") (class "Default")
      (node (ref "U5") (pin "33") (pinfunction "SDO_33") (pintype "bidirectional"))
    )
    (net (code "49") (name "US1_MOSI_TFT") (class "Default")
      (node (ref "U5") (pin "34") (pinfunction "SDA_34") (pintype "bidirectional"))
    )
    (net (code "50") (name "WTIM2_CC1_TFT_BL") (class "Default")
      (node (ref "R13") (pin "P$1") (pinfunction "P$1_P$1") (pintype "bidirectional"))
    )
    (net (code "51") (name "unconnected-(D1-DO-Pad2)") (class "Default")
      (node (ref "D1") (pin "2") (pinfunction "DO_2") (pintype "bidirectional"))
    )
    (net (code "52") (name "unconnected-(U1-PA0-Pad1)") (class "Default")
      (node (ref "U1") (pin "1") (pinfunction "PA0_1") (pintype "bidirectional"))
    )
    (net (code "53") (name "unconnected-(U1-PA1-Pad2)") (class "Default")
      (node (ref "U1") (pin "2") (pinfunction "PA1_2") (pintype "bidirectional"))
    )
    (net (code "54") (name "unconnected-(U1-PA2-Pad3)") (class "Default")
      (node (ref "U1") (pin "3") (pinfunction "PA2_3") (pintype "bidirectional"))
    )
    (net (code "55") (name "unconnected-(U1-PA3-Pad4)") (class "Default")
      (node (ref "U1") (pin "4") (pinfunction "PA3_4") (pintype "bidirectional"))
    )
    (net (code "56") (name "unconnected-(U1-PA4-Pad5)") (class "Default")
      (node (ref "U1") (pin "5") (pinfunction "PA4_5") (pintype "bidirectional"))
    )
    (net (code "57") (name "unconnected-(U1-PA5-Pad6)") (class "Default")
      (node (ref "U1") (pin "6") (pinfunction "PA5_6") (pintype "bidirectional"))
    )
    (net (code "58") (name "unconnected-(U1-PA12-Pad17)") (class "Default")
      (node (ref "U1") (pin "17") (pinfunction "PA12_17") (pintype "bidirectional"))
    )
    (net (code "59") (name "unconnected-(U1-PA13-Pad18)") (class "Default")
      (node (ref "U1") (pin "18") (pinfunction "PA13_18") (pintype "bidirectional"))
    )
    (net (code "60") (name "unconnected-(U1-PA14-Pad19)") (class "Default")
      (node (ref "U1") (pin "19") (pinfunction "PA14_19") (pintype "bidirectional"))
    )
    (net (code "61") (name "unconnected-(U1-PB3-Pad9)") (class "Default")
      (node (ref "U1") (pin "9") (pinfunction "PB3_9") (pintype "bidirectional"))
    )
    (net (code "62") (name "unconnected-(U1-PB4-Pad10)") (class "Default")
      (node (ref "U1") (pin "10") (pinfunction "PB4_10") (pintype "bidirectional"))
    )
    (net (code "63") (name "unconnected-(U1-PB5-Pad11)") (class "Default")
      (node (ref "U1") (pin "11") (pinfunction "PB5_11") (pintype "bidirectional"))
    )
    (net (code "64") (name "unconnected-(U1-PB6-Pad12)") (class "Default")
      (node (ref "U1") (pin "12") (pinfunction "PB6_12") (pintype "bidirectional"))
    )
    (net (code "65") (name "unconnected-(U1-PB11-Pad21)") (class "Default")
      (node (ref "U1") (pin "21") (pinfunction "PB11_21") (pintype "bidirectional"))
    )
    (net (code "66") (name "unconnected-(U1-PC4-Pad13)") (class "Default")
      (node (ref "U1") (pin "13") (pinfunction "PC4_13") (pintype "bidirectional"))
    )
    (net (code "67") (name "unconnected-(U1-PC5-Pad14)") (class "Default")
      (node (ref "U1") (pin "14") (pinfunction "PC5_14") (pintype "bidirectional"))
    )
    (net (code "68") (name "unconnected-(U1-PC6-Pad37)") (class "Default")
      (node (ref "U1") (pin "37") (pinfunction "PC6_37") (pintype "bidirectional"))
    )
    (net (code "69") (name "unconnected-(U1-PC7-Pad38)") (class "Default")
      (node (ref "U1") (pin "38") (pinfunction "PC7_38") (pintype "bidirectional"))
    )
    (net (code "70") (name "unconnected-(U1-PD0-Pad28)") (class "Default")
      (node (ref "U1") (pin "28") (pinfunction "PD0_28") (pintype "bidirectional"))
    )
    (net (code "71") (name "unconnected-(U1-PD1-Pad29)") (class "Default")
      (node (ref "U1") (pin "29") (pinfunction "PD1_29") (pintype "bidirectional"))
    )
    (net (code "72") (name "unconnected-(U1-PD2-Pad30)") (class "Default")
      (node (ref "U1") (pin "30") (pinfunction "PD2_30") (pintype "bidirectional"))
    )
    (net (code "73") (name "unconnected-(U1-PD3-Pad31)") (class "Default")
      (node (ref "U1") (pin "31") (pinfunction "PD3_31") (pintype "bidirectional"))
    )
    (net (code "74") (name "unconnected-(U1-PD4-Pad32)") (class "Default")
      (node (ref "U1") (pin "32") (pinfunction "PD4_32") (pintype "bidirectional"))
    )
    (net (code "75") (name "unconnected-(U1-PD5-Pad33)") (class "Default")
      (node (ref "U1") (pin "33") (pinfunction "PD5_33") (pintype "bidirectional"))
    )
    (net (code "76") (name "unconnected-(U1-PD6-Pad34)") (class "Default")
      (node (ref "U1") (pin "34") (pinfunction "PD6_34") (pintype "bidirectional"))
    )
    (net (code "77") (name "unconnected-(U1-PD7-Pad35)") (class "Default")
      (node (ref "U1") (pin "35") (pinfunction "PD7_35") (pintype "bidirectional"))
    )
    (net (code "78") (name "unconnected-(U1-PD8-Pad36)") (class "Default")
      (node (ref "U1") (pin "36") (pinfunction "PD8_36") (pintype "bidirectional"))
    )
    (net (code "79") (name "unconnected-(U1-PE4-Pad41)") (class "Default")
      (node (ref "U1") (pin "41") (pinfunction "PE4_41") (pintype "bidirectional"))
    )
    (net (code "80") (name "unconnected-(U1-PE5-Pad42)") (class "Default")
      (node (ref "U1") (pin "42") (pinfunction "PE5_42") (pintype "bidirectional"))
    )
    (net (code "81") (name "unconnected-(U1-PE6-Pad43)") (class "Default")
      (node (ref "U1") (pin "43") (pinfunction "PE6_43") (pintype "bidirectional"))
    )
    (net (code "82") (name "unconnected-(U1-PE7-Pad44)") (class "Default")
      (node (ref "U1") (pin "44") (pinfunction "PE7_44") (pintype "bidirectional"))
    )
    (net (code "83") (name "unconnected-(U1-PE8-Pad57)") (class "Default")
      (node (ref "U1") (pin "57") (pinfunction "PE8_57") (pintype "bidirectional"))
    )
    (net (code "84") (name "unconnected-(U1-PE9-Pad58)") (class "Default")
      (node (ref "U1") (pin "58") (pinfunction "PE9_58") (pintype "bidirectional"))
    )
    (net (code "85") (name "unconnected-(U1-PE10-Pad59)") (class "Default")
      (node (ref "U1") (pin "59") (pinfunction "PE10_59") (pintype "bidirectional"))
    )
    (net (code "86") (name "unconnected-(U1-PE11-Pad60)") (class "Default")
      (node (ref "U1") (pin "60") (pinfunction "PE11_60") (pintype "bidirectional"))
    )
    (net (code "87") (name "unconnected-(U1-PE12-Pad61)") (class "Default")
      (node (ref "U1") (pin "61") (pinfunction "PE12_61") (pintype "bidirectional"))
    )
    (net (code "88") (name "unconnected-(U1-PE13-Pad62)") (class "Default")
      (node (ref "U1") (pin "62") (pinfunction "PE13_62") (pintype "bidirectional"))
    )
    (net (code "89") (name "unconnected-(U1-PE14-Pad63)") (class "Default")
      (node (ref "U1") (pin "63") (pinfunction "PE14_63") (pintype "bidirectional"))
    )
    (net (code "90") (name "unconnected-(U1-PE15-Pad64)") (class "Default")
      (node (ref "U1") (pin "64") (pinfunction "PE15_64") (pintype "bidirectional"))
    )
    (net (code "91") (name "unconnected-(U1-PF5-Pad54)") (class "Default")
      (node (ref "U1") (pin "54") (pinfunction "PF5_54") (pintype "bidirectional"))
    )
    (net (code "92") (name "unconnected-(U1-PF10-Pad47)") (class "Default")
      (node (ref "U1") (pin "47") (pinfunction "PF10_47") (pintype "bidirectional"))
    )
    (net (code "93") (name "unconnected-(U1-PF11-Pad48)") (class "Default")
      (node (ref "U1") (pin "48") (pinfunction "PF11_48") (pintype "bidirectional"))
    )
    (net (code "94") (name "unconnected-(U1-PF12-Pad53)") (class "Default")
      (node (ref "U1") (pin "53") (pinfunction "PF12_53") (pintype "bidirectional"))
    )
    (net (code "95") (name "unconnected-(U1-VBUS-Pad52)") (class "Default")
      (node (ref "U1") (pin "52") (pinfunction "VBUS_52") (pintype "bidirectional"))
    )
    (net (code "96") (name "unconnected-(U1-VREGI-Pad45)") (class "Default")
      (node (ref "U1") (pin "45") (pinfunction "VREGI_45") (pintype "bidirectional"))
    )
    (net (code "97") (name "unconnected-(U1-VREGO-Pad46)") (class "Default")
      (node (ref "U1") (pin "46") (pinfunction "VREGO_46") (pintype "bidirectional"))
    )
    (net (code "98") (name "unconnected-(U5-X+{slash}SCL-Pad44)") (class "Default")
      (node (ref "U5") (pin "44") (pinfunction "X+/SCL_44") (pintype "bidirectional"))
    )
    (net (code "99") (name "unconnected-(U5-X-{slash}~{IRQ}-Pad46)") (class "Default")
      (node (ref "U5") (pin "46") (pinfunction "X-/~{IRQ}_46") (pintype "bidirectional"))
    )
    (net (code "100") (name "unconnected-(U5-Y+{slash}SDA-Pad45)") (class "Default")
      (node (ref "U5") (pin "45") (pinfunction "Y+/SDA_45") (pintype "bidirectional"))
    )
    (net (code "101") (name "unconnected-(U5-Y-{slash}~{RST}-Pad47)") (class "Default")
      (node (ref "U5") (pin "47") (pinfunction "Y-/~{RST}_47") (pintype "bidirectional"))
    )
    (net (code "102") (name "~{RESET}") (class "Default")
      (node (ref "U1") (pin "20") (pinfunction "~{RESET}_20") (pintype "bidirectional"))
    )
    (net (code "103") (name "~{TFT_RST}") (class "Default")
      (node (ref "U5") (pin "10") (pinfunction "~{RESET}_10") (pintype "bidirectional"))
    )
  )
)
